# SMATwoPort.net
KiCad netlist of a schematic drawn in EAGLE
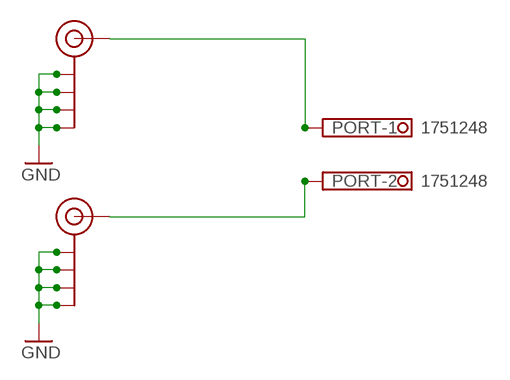
[diagram p0: schematic, sheet 1]

(export (version "E")
  (design (tool "Eeschema 10.0.6"))
  (components
    (comp (ref "J$1")
      (value "SMA_EDGE")
      (footprint "eagle-import:SMA-EDGE")
      (libsource (lib "eagle-import") (part "SMA_EDGE"))
    )
    (comp (ref "J$2")
      (value "SMA_EDGE")
      (footprint "eagle-import:SMA-EDGE")
      (libsource (lib "eagle-import") (part "SMA_EDGE"))
    )
    (comp (ref "PORT")
      (value "1751248")
      (footprint "eagle-import:1751248")
      (libsource (lib "eagle-import") (part "1751248"))
    )
  )
  (nets
    (net (code "1") (name "GND") (class "Default")
      (node (ref "J$1") (pin "GND@0") (pinfunction "GND_GND@0") (pintype "bidirectional"))
      (node (ref "J$1") (pin "GND@1") (pinfunction "GND_GND@1") (pintype "bidirectional"))
      (node (ref "J$1") (pin "GND@2") (pinfunction "GND_GND@2") (pintype "bidirectional"))
      (node (ref "J$1") (pin "GND@3") (pinfunction "GND_GND@3") (pintype "bidirectional"))
      (node (ref "J$2") (pin "GND@0") (pinfunction "GND_GND@0") (pintype "bidirectional"))
      (node (ref "J$2") (pin "GND@1") (pinfunction "GND_GND@1") (pintype "bidirectional"))
      (node (ref "J$2") (pin "GND@2") (pinfunction "GND_GND@2") (pintype "bidirectional"))
      (node (ref "J$2") (pin "GND@3") (pinfunction "GND_GND@3") (pintype "bidirectional"))
    )
    (net (code "2") (name "Net-(J$1-SIGNAL)") (class "Default")
      (node (ref "J$1") (pin "SIG") (pinfunction "SIGNAL_SIG") (pintype "bidirectional"))
      (node (ref "PORT") (pin "2") (pinfunction "K_2") (pintype "passive"))
    )
    (net (code "3") (name "Net-(J$2-SIGNAL)") (class "Default")
      (node (ref "J$2") (pin "SIG") (pinfunction "SIGNAL_SIG") (pintype "bidirectional"))
      (node (ref "PORT") (pin "1") (pinfunction "K_1") (pintype "passive"))
    )
  )
)
